# echo-ltt.net
KiCad netlist of a schematic drawn in EAGLE
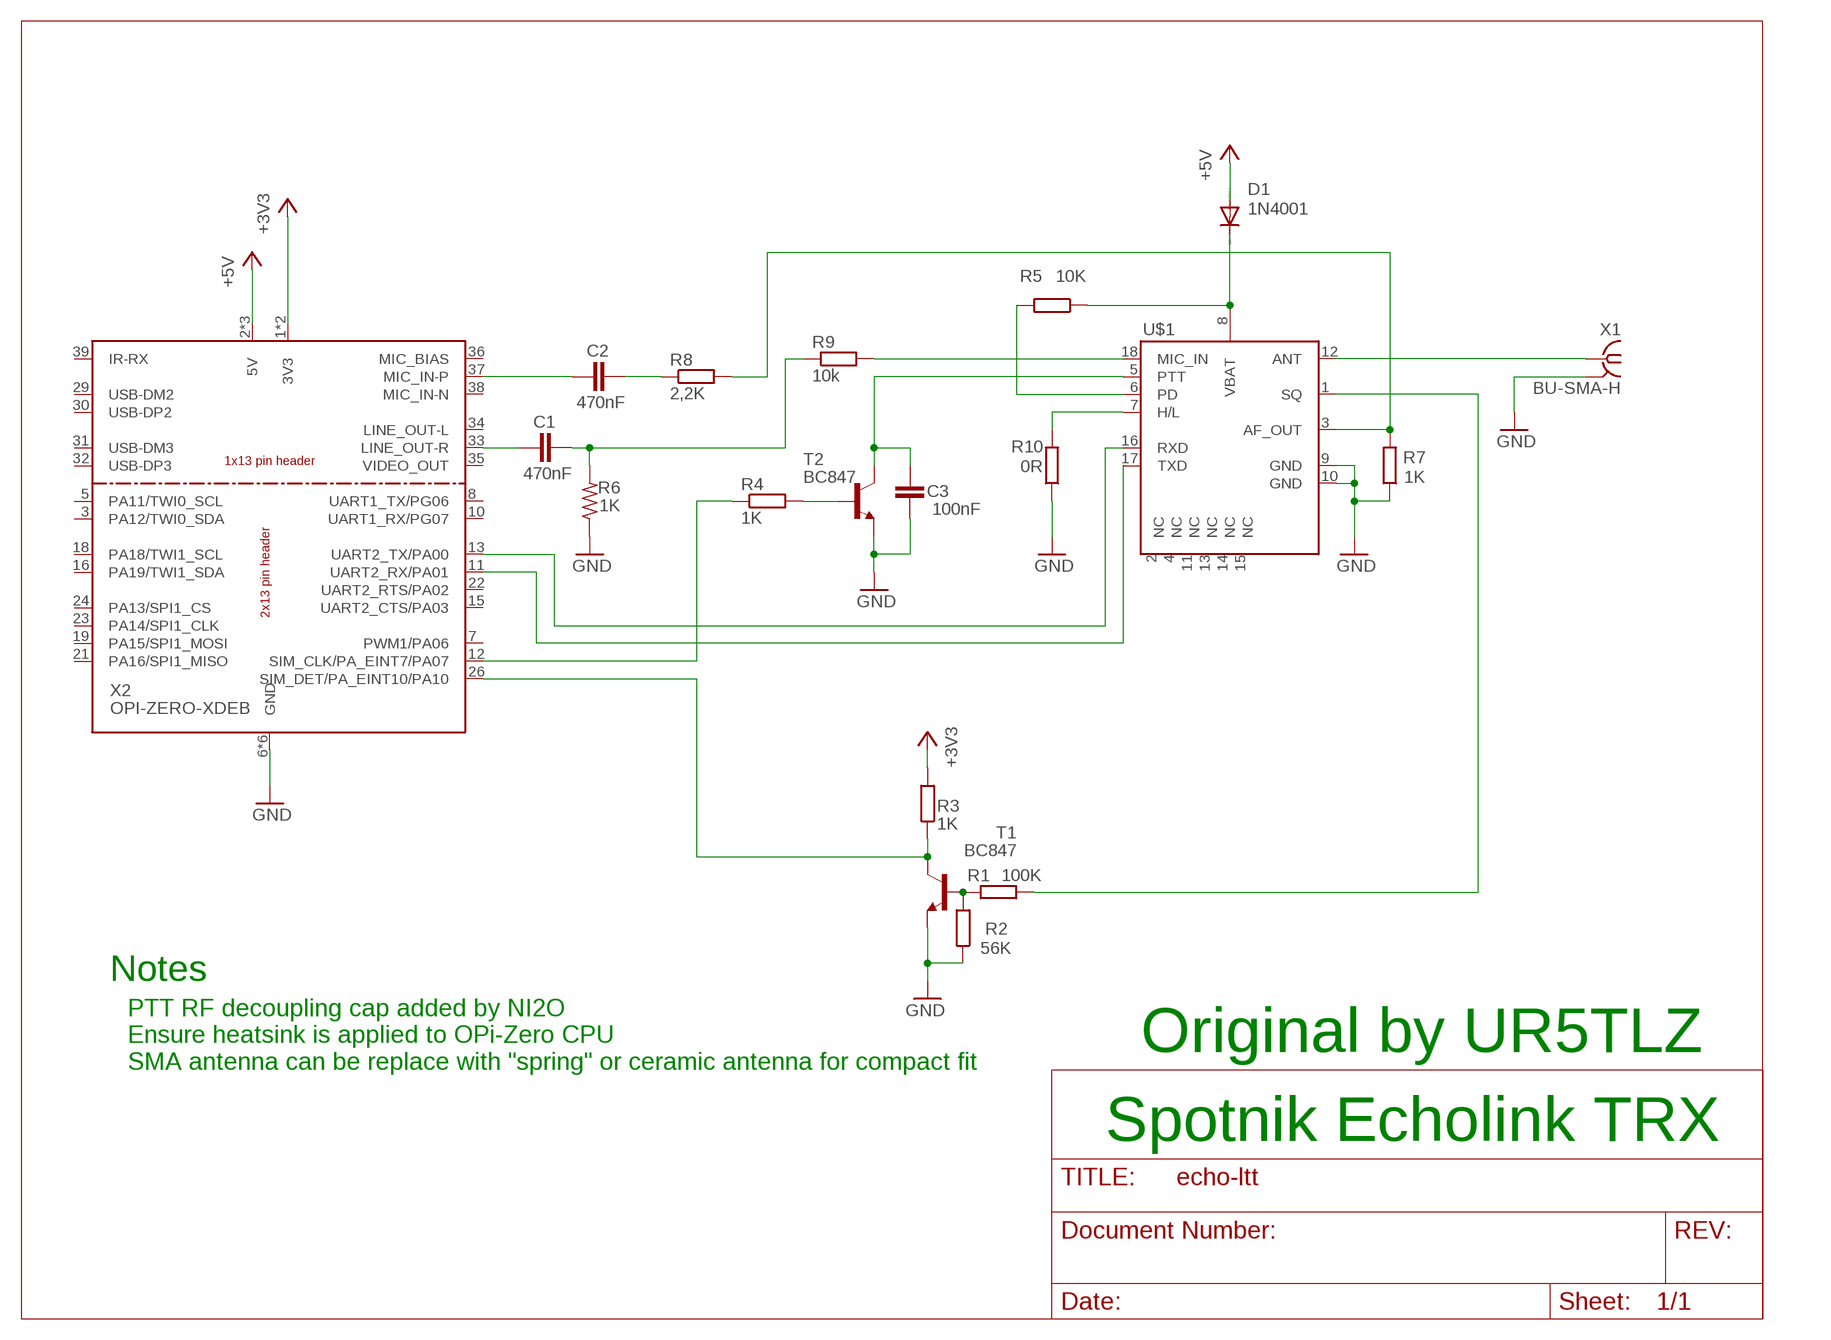
[diagram p0: schematic, sheet 1]

(export (version "E")
  (design (tool "Eeschema 10.0.6"))
  (components
    (comp (ref "C1")
      (value "470nF")
      (footprint "eagle-import:C0805")
      (libsource (lib "eagle-import") (part "C-EUC0805"))
    )
    (comp (ref "C2")
      (value "470nF")
      (footprint "eagle-import:C0805")
      (libsource (lib "eagle-import") (part "C-EUC0805"))
    )
    (comp (ref "C3")
      (value "100nF")
      (footprint "eagle-import:C0805")
      (libsource (lib "eagle-import") (part "C-EUC0805"))
    )
    (comp (ref "D1")
      (value "1N4001")
      (footprint "eagle-import:DO41-10")
      (libsource (lib "eagle-import") (part "DIODE-DO41-10"))
    )
    (comp (ref "R1")
      (value "100K")
      (footprint "eagle-import:R0805")
      (libsource (lib "eagle-import") (part "R-EU_R0805"))
    )
    (comp (ref "R2")
      (value "56K")
      (footprint "eagle-import:R0805")
      (libsource (lib "eagle-import") (part "R-EU_R0805"))
    )
    (comp (ref "R3")
      (value "1K")
      (footprint "eagle-import:R0805")
      (libsource (lib "eagle-import") (part "R-EU_R0805"))
    )
    (comp (ref "R4")
      (value "1K")
      (footprint "eagle-import:R0805")
      (libsource (lib "eagle-import") (part "R-EU_R0805"))
    )
    (comp (ref "R5")
      (value "10K")
      (footprint "eagle-import:R0805")
      (libsource (lib "eagle-import") (part "R-EU_R0805"))
    )
    (comp (ref "R6")
      (value "1K")
      (footprint "eagle-import:R0805")
      (libsource (lib "eagle-import") (part "R-US_R0805"))
    )
    (comp (ref "R7")
      (value "1K")
      (footprint "eagle-import:R0805")
      (libsource (lib "eagle-import") (part "R-EU_R0805"))
    )
    (comp (ref "R8")
      (value "2,2K")
      (footprint "eagle-import:R0805")
      (libsource (lib "eagle-import") (part "R-EU_R0805"))
    )
    (comp (ref "R9")
      (value "10k")
      (footprint "eagle-import:R0805")
      (libsource (lib "eagle-import") (part "R-EU_R0805"))
    )
    (comp (ref "R10")
      (value "0R")
      (footprint "eagle-import:R0805")
      (libsource (lib "eagle-import") (part "R-EU_R0805"))
    )
    (comp (ref "T1")
      (value "BC847")
      (footprint "eagle-import:SOT23")
      (libsource (lib "eagle-import") (part "BC847"))
    )
    (comp (ref "T2")
      (value "BC847")
      (footprint "eagle-import:SOT23")
      (libsource (lib "eagle-import") (part "BC847"))
    )
    (comp (ref "U$1")
      (value "DRA818A")
      (footprint "eagle-import:DRA818A")
      (libsource (lib "eagle-import") (part "DRA818A"))
    )
    (comp (ref "X1")
      (value "BU-SMA-H")
      (footprint "eagle-import:BU-SMA-H")
      (libsource (lib "eagle-import") (part "BU-SMA-H"))
    )
    (comp (ref "X2")
      (value "OPI-ZERO-XDEB")
      (footprint "eagle-import:OPIOHATDEB")
      (libsource (lib "eagle-import") (part "OPI-ZERO-XDEB"))
    )
  )
  (nets
    (net (code "1") (name "+3V3") (class "Default")
      (node (ref "R3") (pin "2") (pinfunction "2_2") (pintype "passive"))
      (node (ref "X2") (pin "1") (pinfunction "3V3_1") (pintype "power_in"))
      (node (ref "X2") (pin "17") (pinfunction "3V3_17") (pintype "power_in"))
    )
    (net (code "2") (name "+5V") (class "Default")
      (node (ref "D1") (pin "A") (pinfunction "A_A") (pintype "passive"))
      (node (ref "X2") (pin "2") (pinfunction "5V_2") (pintype "power_in"))
      (node (ref "X2") (pin "27") (pinfunction "5V_27") (pintype "power_in"))
      (node (ref "X2") (pin "4") (pinfunction "5V_4") (pintype "power_in"))
    )
    (net (code "3") (name "GND") (class "Default")
      (node (ref "C3") (pin "2") (pinfunction "2_2") (pintype "passive"))
      (node (ref "R10") (pin "1") (pinfunction "1_1") (pintype "passive"))
      (node (ref "R2") (pin "1") (pinfunction "1_1") (pintype "passive"))
      (node (ref "R6") (pin "1") (pinfunction "1_1") (pintype "passive"))
      (node (ref "R7") (pin "1") (pinfunction "1_1") (pintype "passive"))
      (node (ref "T1") (pin "2") (pinfunction "E_2") (pintype "passive"))
      (node (ref "T2") (pin "2") (pinfunction "E_2") (pintype "passive"))
      (node (ref "U$1") (pin "10") (pinfunction "GND_10") (pintype "bidirectional"))
      (node (ref "U$1") (pin "9") (pinfunction "GND_9") (pintype "bidirectional"))
      (node (ref "X1") (pin "2") (pinfunction "2_2") (pintype "passive"))
      (node (ref "X1") (pin "3") (pinfunction "2_3") (pintype "passive"))
      (node (ref "X1") (pin "4") (pinfunction "2_4") (pintype "passive"))
      (node (ref "X1") (pin "5") (pinfunction "2_5") (pintype "passive"))
      (node (ref "X2") (pin "14") (pinfunction "GND_14") (pintype "power_in"))
      (node (ref "X2") (pin "20") (pinfunction "GND_20") (pintype "power_in"))
      (node (ref "X2") (pin "25") (pinfunction "GND_25") (pintype "power_in"))
      (node (ref "X2") (pin "28") (pinfunction "GND_28") (pintype "power_in"))
      (node (ref "X2") (pin "6") (pinfunction "GND_6") (pintype "power_in"))
      (node (ref "X2") (pin "9") (pinfunction "GND_9") (pintype "power_in"))
    )
    (net (code "4") (name "Net-(C1-Pad1)") (class "Default")
      (node (ref "C1") (pin "1") (pinfunction "1_1") (pintype "passive"))
      (node (ref "R6") (pin "2") (pinfunction "2_2") (pintype "passive"))
      (node (ref "R9") (pin "1") (pinfunction "1_1") (pintype "passive"))
    )
    (net (code "5") (name "Net-(C2-Pad1)") (class "Default")
      (node (ref "C2") (pin "1") (pinfunction "1_1") (pintype "passive"))
      (node (ref "R8") (pin "1") (pinfunction "1_1") (pintype "passive"))
    )
    (net (code "6") (name "Net-(T1-B)") (class "Default")
      (node (ref "R1") (pin "2") (pinfunction "2_2") (pintype "passive"))
      (node (ref "R2") (pin "2") (pinfunction "2_2") (pintype "passive"))
      (node (ref "T1") (pin "1") (pinfunction "B_1") (pintype "passive"))
    )
    (net (code "7") (name "Net-(T1-C)") (class "Default")
      (node (ref "R3") (pin "1") (pinfunction "1_1") (pintype "passive"))
      (node (ref "T1") (pin "3") (pinfunction "C_3") (pintype "passive"))
      (node (ref "X2") (pin "26") (pinfunction "SIM_DET/PA_EINT10/PA10_26") (pintype "bidirectional"))
    )
    (net (code "8") (name "Net-(T2-B)") (class "Default")
      (node (ref "R4") (pin "2") (pinfunction "2_2") (pintype "passive"))
      (node (ref "T2") (pin "1") (pinfunction "B_1") (pintype "passive"))
    )
    (net (code "9") (name "Net-(T2-C)") (class "Default")
      (node (ref "C3") (pin "1") (pinfunction "1_1") (pintype "passive"))
      (node (ref "T2") (pin "3") (pinfunction "C_3") (pintype "passive"))
      (node (ref "U$1") (pin "5") (pinfunction "PTT_5") (pintype "bidirectional"))
    )
    (net (code "10") (name "Net-(U$1-AF_OUT)") (class "Default")
      (node (ref "R7") (pin "2") (pinfunction "2_2") (pintype "passive"))
      (node (ref "R8") (pin "2") (pinfunction "2_2") (pintype "passive"))
      (node (ref "U$1") (pin "3") (pinfunction "AF_OUT_3") (pintype "bidirectional"))
    )
    (net (code "11") (name "Net-(U$1-ANT)") (class "Default")
      (node (ref "U$1") (pin "12") (pinfunction "ANT_12") (pintype "bidirectional"))
      (node (ref "X1") (pin "1") (pinfunction "1_1") (pintype "passive"))
    )
    (net (code "12") (name "Net-(U$1-H{slash}L)") (class "Default")
      (node (ref "R10") (pin "2") (pinfunction "2_2") (pintype "passive"))
      (node (ref "U$1") (pin "7") (pinfunction "H/L_7") (pintype "bidirectional"))
    )
    (net (code "13") (name "Net-(U$1-MIC_IN)") (class "Default")
      (node (ref "R9") (pin "2") (pinfunction "2_2") (pintype "passive"))
      (node (ref "U$1") (pin "18") (pinfunction "MIC_IN_18") (pintype "bidirectional"))
    )
    (net (code "14") (name "Net-(U$1-PD)") (class "Default")
      (node (ref "R5") (pin "2") (pinfunction "2_2") (pintype "passive"))
      (node (ref "U$1") (pin "6") (pinfunction "PD_6") (pintype "bidirectional"))
    )
    (net (code "15") (name "Net-(U$1-RXD)") (class "Default")
      (node (ref "U$1") (pin "16") (pinfunction "RXD_16") (pintype "bidirectional"))
      (node (ref "X2") (pin "13") (pinfunction "UART2_TX/PA00_13") (pintype "bidirectional"))
    )
    (net (code "16") (name "Net-(U$1-SQ)") (class "Default")
      (node (ref "R1") (pin "1") (pinfunction "1_1") (pintype "passive"))
      (node (ref "U$1") (pin "1") (pinfunction "SQ_1") (pintype "bidirectional"))
    )
    (net (code "17") (name "Net-(U$1-TXD)") (class "Default")
      (node (ref "U$1") (pin "17") (pinfunction "TXD_17") (pintype "bidirectional"))
      (node (ref "X2") (pin "11") (pinfunction "UART2_RX/PA01_11") (pintype "bidirectional"))
    )
    (net (code "18") (name "Net-(U$1-VBAT)") (class "Default")
      (node (ref "D1") (pin "C") (pinfunction "C_C") (pintype "passive"))
      (node (ref "R5") (pin "1") (pinfunction "1_1") (pintype "passive"))
      (node (ref "U$1") (pin "8") (pinfunction "VBAT_8") (pintype "bidirectional"))
    )
    (net (code "19") (name "Net-(X2-LINE_OUT-R)") (class "Default")
      (node (ref "C1") (pin "2") (pinfunction "2_2") (pintype "passive"))
      (node (ref "X2") (pin "33") (pinfunction "LINE_OUT-R_33") (pintype "passive"))
    )
    (net (code "20") (name "Net-(X2-MIC_IN-P)") (class "Default")
      (node (ref "C2") (pin "2") (pinfunction "2_2") (pintype "passive"))
      (node (ref "X2") (pin "37") (pinfunction "MIC_IN-P_37") (pintype "passive"))
    )
    (net (code "21") (name "Net-(X2-SIM_CLK{slash}PA_EINT7{slash}PA07)") (class "Default")
      (node (ref "R4") (pin "1") (pinfunction "1_1") (pintype "passive"))
      (node (ref "X2") (pin "12") (pinfunction "SIM_CLK/PA_EINT7/PA07_12") (pintype "bidirectional"))
    )
    (net (code "22") (name "unconnected-(U$1-NC-Pad2)") (class "Default")
      (node (ref "U$1") (pin "2") (pinfunction "NC_2") (pintype "bidirectional"))
    )
    (net (code "23") (name "unconnected-(U$1-NC-Pad4)") (class "Default")
      (node (ref "U$1") (pin "4") (pinfunction "NC_4") (pintype "bidirectional"))
    )
    (net (code "24") (name "unconnected-(U$1-NC-Pad11)") (class "Default")
      (node (ref "U$1") (pin "11") (pinfunction "NC_11") (pintype "bidirectional"))
    )
    (net (code "25") (name "unconnected-(U$1-NC-Pad13)") (class "Default")
      (node (ref "U$1") (pin "13") (pinfunction "NC_13") (pintype "bidirectional"))
    )
    (net (code "26") (name "unconnected-(U$1-NC-Pad14)") (class "Default")
      (node (ref "U$1") (pin "14") (pinfunction "NC_14") (pintype "bidirectional"))
    )
    (net (code "27") (name "unconnected-(U$1-NC-Pad15)") (class "Default")
      (node (ref "U$1") (pin "15") (pinfunction "NC_15") (pintype "bidirectional"))
    )
    (net (code "28") (name "unconnected-(X2-IR-RX-Pad39)") (class "Default")
      (node (ref "X2") (pin "39") (pinfunction "IR-RX_39") (pintype "passive"))
    )
    (net (code "29") (name "unconnected-(X2-LINE_OUT-L-Pad34)") (class "Default")
      (node (ref "X2") (pin "34") (pinfunction "LINE_OUT-L_34") (pintype "passive"))
    )
    (net (code "30") (name "unconnected-(X2-MIC_BIAS-Pad36)") (class "Default")
      (node (ref "X2") (pin "36") (pinfunction "MIC_BIAS_36") (pintype "passive"))
    )
    (net (code "31") (name "unconnected-(X2-MIC_IN-N-Pad38)") (class "Default")
      (node (ref "X2") (pin "38") (pinfunction "MIC_IN-N_38") (pintype "passive"))
    )
    (net (code "32") (name "unconnected-(X2-PA11{slash}TWI0_SCL-Pad5)") (class "Default")
      (node (ref "X2") (pin "5") (pinfunction "PA11/TWI0_SCL_5") (pintype "bidirectional"))
    )
    (net (code "33") (name "unconnected-(X2-PA12{slash}TWI0_SDA-Pad3)") (class "Default")
      (node (ref "X2") (pin "3") (pinfunction "PA12/TWI0_SDA_3") (pintype "bidirectional"))
    )
    (net (code "34") (name "unconnected-(X2-PA13{slash}SPI1_CS-Pad24)") (class "Default")
      (node (ref "X2") (pin "24") (pinfunction "PA13/SPI1_CS_24") (pintype "bidirectional"))
    )
    (net (code "35") (name "unconnected-(X2-PA14{slash}SPI1_CLK-Pad23)") (class "Default")
      (node (ref "X2") (pin "23") (pinfunction "PA14/SPI1_CLK_23") (pintype "bidirectional"))
    )
    (net (code "36") (name "unconnected-(X2-PA15{slash}SPI1_MOSI-Pad19)") (class "Default")
      (node (ref "X2") (pin "19") (pinfunction "PA15/SPI1_MOSI_19") (pintype "bidirectional"))
    )
    (net (code "37") (name "unconnected-(X2-PA16{slash}SPI1_MISO-Pad21)") (class "Default")
      (node (ref "X2") (pin "21") (pinfunction "PA16/SPI1_MISO_21") (pintype "bidirectional"))
    )
    (net (code "38") (name "unconnected-(X2-PA18{slash}TWI1_SCL-Pad18)") (class "Default")
      (node (ref "X2") (pin "18") (pinfunction "PA18/TWI1_SCL_18") (pintype "bidirectional"))
    )
    (net (code "39") (name "unconnected-(X2-PA19{slash}TWI1_SDA-Pad16)") (class "Default")
      (node (ref "X2") (pin "16") (pinfunction "PA19/TWI1_SDA_16") (pintype "bidirectional"))
    )
    (net (code "40") (name "unconnected-(X2-PWM1{slash}PA06-Pad7)") (class "Default")
      (node (ref "X2") (pin "7") (pinfunction "PWM1/PA06_7") (pintype "bidirectional"))
    )
    (net (code "41") (name "unconnected-(X2-UART1_RX{slash}PG07-Pad10)") (class "Default")
      (node (ref "X2") (pin "10") (pinfunction "UART1_RX/PG07_10") (pintype "bidirectional"))
    )
    (net (code "42") (name "unconnected-(X2-UART1_TX{slash}PG06-Pad8)") (class "Default")
      (node (ref "X2") (pin "8") (pinfunction "UART1_TX/PG06_8") (pintype "bidirectional"))
    )
    (net (code "43") (name "unconnected-(X2-UART2_CTS{slash}PA03-Pad15)") (class "Default")
      (node (ref "X2") (pin "15") (pinfunction "UART2_CTS/PA03_15") (pintype "bidirectional"))
    )
    (net (code "44") (name "unconnected-(X2-UART2_RTS{slash}PA02-Pad22)") (class "Default")
      (node (ref "X2") (pin "22") (pinfunction "UART2_RTS/PA02_22") (pintype "bidirectional"))
    )
    (net (code "45") (name "unconnected-(X2-USB-DM2-Pad29)") (class "Default")
      (node (ref "X2") (pin "29") (pinfunction "USB-DM2_29") (pintype "bidirectional"))
    )
    (net (code "46") (name "unconnected-(X2-USB-DM3-Pad31)") (class "Default")
      (node (ref "X2") (pin "31") (pinfunction "USB-DM3_31") (pintype "bidirectional"))
    )
    (net (code "47") (name "unconnected-(X2-USB-DP2-Pad30)") (class "Default")
      (node (ref "X2") (pin "30") (pinfunction "USB-DP2_30") (pintype "bidirectional"))
    )
    (net (code "48") (name "unconnected-(X2-USB-DP3-Pad32)") (class "Default")
      (node (ref "X2") (pin "32") (pinfunction "USB-DP3_32") (pintype "bidirectional"))
    )
    (net (code "49") (name "unconnected-(X2-VIDEO_OUT-Pad35)") (class "Default")
      (node (ref "X2") (pin "35") (pinfunction "VIDEO_OUT_35") (pintype "passive"))
    )
  )
)
